# Sheet-2.net
KiCad netlist of a schematic drawn in Altium Designer
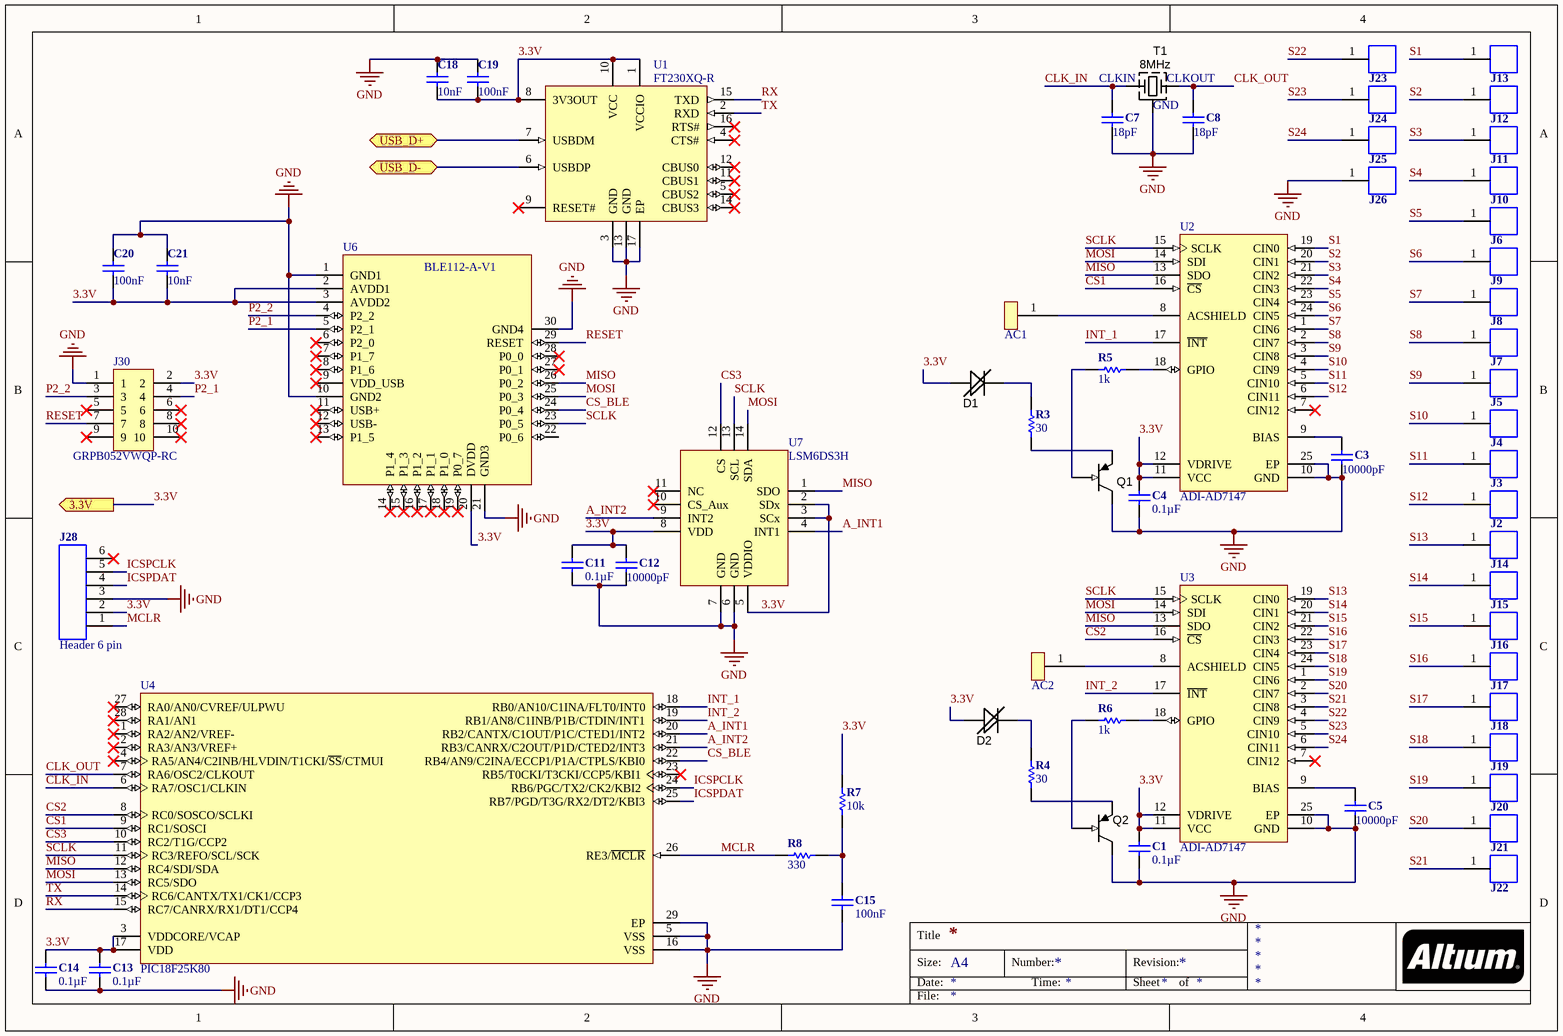
[diagram p0: Sheet-2.SchDoc]

(export (version "E")
  (design (tool "Eeschema 10.0.6"))
  (components
    (comp (ref "AC1")
      (value "AC_Shield")
      (footprint "AC_SHIELD")
      (libsource (lib "Glove") (part "AC_Shield"))
    )
    (comp (ref "AC2")
      (value "AC_Shield")
      (footprint "AC_SHIELD")
      (libsource (lib "Glove") (part "AC_Shield"))
    )
    (comp (ref "C1")
      (value "0.1µF")
      (footprint "CAP-0805(2012)-R")
      (description "___ OHM ___ mW 0805(2012) SMD")
      (fields
        (field (name "MANUFACTURER") "Yageo")
        (field (name "MANUFACTURER PART NUMBER") "CC0805KRX7R9BB104")
      )
      (libsource (lib "Glove") (part "C-0805(2012)"))
    )
    (comp (ref "C3")
      (value "10000pF")
      (footprint "CAP-0805(2012)-R")
      (description "___ OHM ___ mW 0805(2012) SMD")
      (fields
        (field (name "MANUFACTURER") "Yageo")
        (field (name "MANUFACTURER PART NUMBER") "CC0805KRX7R9BB103")
      )
      (libsource (lib "Glove") (part "C-0805(2012)"))
    )
    (comp (ref "C4")
      (value "0.1µF")
      (footprint "CAP-0805(2012)-R")
      (description "___ OHM ___ mW 0805(2012) SMD")
      (fields
        (field (name "MANUFACTURER") "Yageo")
        (field (name "MANUFACTURER PART NUMBER") "CC0805KRX7R9BB104")
      )
      (libsource (lib "Glove") (part "C-0805(2012)"))
    )
    (comp (ref "C5")
      (value "10000pF")
      (footprint "CAP-0805(2012)-R")
      (description "___ OHM ___ mW 0805(2012) SMD")
      (fields
        (field (name "MANUFACTURER") "Yageo")
        (field (name "MANUFACTURER PART NUMBER") "CC0805KRX7R9BB103")
      )
      (libsource (lib "Glove") (part "C-0805(2012)"))
    )
    (comp (ref "C7")
      (value "18pF")
      (footprint "CAP-0805(2012)-R")
      (description "___ OHM ___ mW 0805(2012) SMD")
      (fields
        (field (name "MANUFACTURER") "Yageo")
        (field (name "MANUFACTURER PART NUMBER") "CC0805JRNPO9BN180")
      )
      (libsource (lib "Glove") (part "C-0805(2012)"))
    )
    (comp (ref "C8")
      (value "18pF")
      (footprint "CAP-0805(2012)-R")
      (description "___ OHM ___ mW 0805(2012) SMD")
      (fields
        (field (name "MANUFACTURER") "Yageo")
        (field (name "MANUFACTURER PART NUMBER") "CC0805JRNPO9BN180")
      )
      (libsource (lib "Glove") (part "C-0805(2012)"))
    )
    (comp (ref "C11")
      (value "0.1µF")
      (footprint "CAP-0805(2012)-R")
      (description "___ OHM ___ mW 0805(2012) SMD")
      (fields
        (field (name "MANUFACTURER") "Yageo")
        (field (name "MANUFACTURER PART NUMBER") "CC0805KRX7R9BB104")
      )
      (libsource (lib "Glove") (part "C-0805(2012)"))
    )
    (comp (ref "C12")
      (value "10000pF")
      (footprint "CAP-0805(2012)-R")
      (description "___ OHM ___ mW 0805(2012) SMD")
      (fields
        (field (name "MANUFACTURER") "Yageo")
        (field (name "MANUFACTURER PART NUMBER") "CC0805KRX7R9BB103")
      )
      (libsource (lib "Glove") (part "C-0805(2012)"))
    )
    (comp (ref "C13")
      (value "0.1µF")
      (footprint "CAP-0805(2012)-R")
      (description "___ OHM ___ mW 0805(2012) SMD")
      (fields
        (field (name "MANUFACTURER") "Yageo")
        (field (name "MANUFACTURER PART NUMBER") "CC0805KRX7R9BB104")
      )
      (libsource (lib "Glove") (part "C-0805(2012)"))
    )
    (comp (ref "C14")
      (value "0.1µF")
      (footprint "CAP-0805(2012)-R")
      (description "___ OHM ___ mW 0805(2012) SMD")
      (fields
        (field (name "MANUFACTURER") "Yageo")
        (field (name "MANUFACTURER PART NUMBER") "CC0805KRX7R9BB104")
      )
      (libsource (lib "Glove") (part "C-0805(2012)"))
    )
    (comp (ref "C15")
      (value "100nF")
      (footprint "CAP-0805(2012)-R")
      (description "___ OHM ___ mW 0805(2012) SMD")
      (fields
        (field (name "MANUFACTURER") "Yageo")
        (field (name "MANUFACTURER PART NUMBER") "CC0805KRX7R9BB104")
      )
      (libsource (lib "Glove") (part "C-0805(2012)"))
    )
    (comp (ref "C18")
      (value "10nF")
      (footprint "CAP-0805(2012)-R")
      (description "___ OHM ___ mW 0805(2012) SMD")
      (fields
        (field (name "MANUFACTURER") "Yageo")
        (field (name "MANUFACTURER PART NUMBER") "CC0805KRX7R9BB103")
      )
      (libsource (lib "Glove") (part "C-0805(2012)"))
    )
    (comp (ref "C19")
      (value "100nF")
      (footprint "CAP-0805(2012)-R")
      (description "___ OHM ___ mW 0805(2012) SMD")
      (fields
        (field (name "MANUFACTURER") "Yageo")
        (field (name "MANUFACTURER PART NUMBER") "CC0805KRX7R9BB104")
      )
      (libsource (lib "Glove") (part "C-0805(2012)"))
    )
    (comp (ref "C20")
      (value "100nF")
      (footprint "CAP-0805(2012)-R")
      (description "___ OHM ___ mW 0805(2012) SMD")
      (fields
        (field (name "MANUFACTURER") "Yageo")
        (field (name "MANUFACTURER PART NUMBER") "CC0805KRX7R9BB104")
      )
      (libsource (lib "Glove") (part "C-0805(2012)"))
    )
    (comp (ref "C21")
      (value "10nF")
      (footprint "CAP-0805(2012)-R")
      (description "___ OHM ___ mW 0805(2012) SMD")
      (fields
        (field (name "MANUFACTURER") "Yageo")
        (field (name "MANUFACTURER PART NUMBER") "CC0805KRX7R9BB103")
      )
      (libsource (lib "Glove") (part "C-0805(2012)"))
    )
    (comp (ref "D1")
      (value "YELLOW")
      (footprint "LED-0805-A")
      (description "LED, 0805 SMD, YELLOW")
      (fields
        (field (name "MANUFACTURER") "OSRAM Opto Semiconductors Inc.")
        (field (name "MANUFACTURER PART NUMBER") "LY R976-PS-36")
      )
      (libsource (lib "Glove") (part "LED_0805_YELLOW"))
    )
    (comp (ref "D2")
      (value "YELLOW")
      (footprint "LED-0805-A")
      (description "LED, 0805 SMD, YELLOW")
      (fields
        (field (name "MANUFACTURER") "OSRAM Opto Semiconductors Inc.")
        (field (name "MANUFACTURER PART NUMBER") "LY R976-PS-36")
      )
      (libsource (lib "Glove") (part "LED_0805_YELLOW"))
    )
    (comp (ref "J2")
      (value "Conductive Thread")
      (footprint "THREAD_HOLE")
      (description "Header, 1 pin, Conductive Thread")
      (libsource (lib "Glove") (part "CON-1_Pin_Thread"))
    )
    (comp (ref "J3")
      (value "Conductive Thread")
      (footprint "THREAD_HOLE")
      (description "Header, 1 pin, Conductive Thread")
      (libsource (lib "Glove") (part "CON-1_Pin_Thread"))
    )
    (comp (ref "J4")
      (value "Conductive Thread")
      (footprint "THREAD_HOLE")
      (description "Header, 1 pin, Conductive Thread")
      (libsource (lib "Glove") (part "CON-1_Pin_Thread"))
    )
    (comp (ref "J5")
      (value "Conductive Thread")
      (footprint "THREAD_HOLE")
      (description "Header, 1 pin, Conductive Thread")
      (libsource (lib "Glove") (part "CON-1_Pin_Thread"))
    )
    (comp (ref "J6")
      (value "Conductive Thread")
      (footprint "THREAD_HOLE")
      (description "Header, 1 pin, Conductive Thread")
      (libsource (lib "Glove") (part "CON-1_Pin_Thread"))
    )
    (comp (ref "J7")
      (value "Conductive Thread")
      (footprint "THREAD_HOLE")
      (description "Header, 1 pin, Conductive Thread")
      (libsource (lib "Glove") (part "CON-1_Pin_Thread"))
    )
    (comp (ref "J8")
      (value "Conductive Thread")
      (footprint "THREAD_HOLE")
      (description "Header, 1 pin, Conductive Thread")
      (libsource (lib "Glove") (part "CON-1_Pin_Thread"))
    )
    (comp (ref "J9")
      (value "Conductive Thread")
      (footprint "THREAD_HOLE")
      (description "Header, 1 pin, Conductive Thread")
      (libsource (lib "Glove") (part "CON-1_Pin_Thread"))
    )
    (comp (ref "J10")
      (value "Conductive Thread")
      (footprint "THREAD_HOLE")
      (description "Header, 1 pin, Conductive Thread")
      (libsource (lib "Glove") (part "CON-1_Pin_Thread"))
    )
    (comp (ref "J11")
      (value "Conductive Thread")
      (footprint "THREAD_HOLE")
      (description "Header, 1 pin, Conductive Thread")
      (libsource (lib "Glove") (part "CON-1_Pin_Thread"))
    )
    (comp (ref "J12")
      (value "Conductive Thread")
      (footprint "THREAD_HOLE")
      (description "Header, 1 pin, Conductive Thread")
      (libsource (lib "Glove") (part "CON-1_Pin_Thread"))
    )
    (comp (ref "J13")
      (value "Conductive Thread")
      (footprint "THREAD_HOLE")
      (description "Header, 1 pin, Conductive Thread")
      (libsource (lib "Glove") (part "CON-1_Pin_Thread"))
    )
    (comp (ref "J14")
      (value "Conductive Thread")
      (footprint "THREAD_HOLE")
      (description "Header, 1 pin, Conductive Thread")
      (libsource (lib "Glove") (part "CON-1_Pin_Thread"))
    )
    (comp (ref "J15")
      (value "Conductive Thread")
      (footprint "THREAD_HOLE")
      (description "Header, 1 pin, Conductive Thread")
      (libsource (lib "Glove") (part "CON-1_Pin_Thread"))
    )
    (comp (ref "J16")
      (value "Conductive Thread")
      (footprint "THREAD_HOLE")
      (description "Header, 1 pin, Conductive Thread")
      (libsource (lib "Glove") (part "CON-1_Pin_Thread"))
    )
    (comp (ref "J17")
      (value "Conductive Thread")
      (footprint "THREAD_HOLE")
      (description "Header, 1 pin, Conductive Thread")
      (libsource (lib "Glove") (part "CON-1_Pin_Thread"))
    )
    (comp (ref "J18")
      (value "Conductive Thread")
      (footprint "THREAD_HOLE")
      (description "Header, 1 pin, Conductive Thread")
      (libsource (lib "Glove") (part "CON-1_Pin_Thread"))
    )
    (comp (ref "J19")
      (value "Conductive Thread")
      (footprint "THREAD_HOLE")
      (description "Header, 1 pin, Conductive Thread")
      (libsource (lib "Glove") (part "CON-1_Pin_Thread"))
    )
    (comp (ref "J20")
      (value "Conductive Thread")
      (footprint "THREAD_HOLE")
      (description "Header, 1 pin, Conductive Thread")
      (libsource (lib "Glove") (part "CON-1_Pin_Thread"))
    )
    (comp (ref "J21")
      (value "Conductive Thread")
      (footprint "THREAD_HOLE")
      (description "Header, 1 pin, Conductive Thread")
      (libsource (lib "Glove") (part "CON-1_Pin_Thread"))
    )
    (comp (ref "J22")
      (value "Conductive Thread")
      (footprint "THREAD_HOLE")
      (description "Header, 1 pin, Conductive Thread")
      (libsource (lib "Glove") (part "CON-1_Pin_Thread"))
    )
    (comp (ref "J23")
      (value "Conductive Thread")
      (footprint "THREAD_HOLE")
      (description "Header, 1 pin, Conductive Thread")
      (libsource (lib "Glove") (part "CON-1_Pin_Thread"))
    )
    (comp (ref "J24")
      (value "Conductive Thread")
      (footprint "THREAD_HOLE")
      (description "Header, 1 pin, Conductive Thread")
      (libsource (lib "Glove") (part "CON-1_Pin_Thread"))
    )
    (comp (ref "J25")
      (value "Conductive Thread")
      (footprint "THREAD_HOLE")
      (description "Header, 1 pin, Conductive Thread")
      (libsource (lib "Glove") (part "CON-1_Pin_Thread"))
    )
    (comp (ref "J26")
      (value "Conductive Thread")
      (footprint "THREAD_HOLE")
      (description "Header, 1 pin, Conductive Thread")
      (libsource (lib "Glove") (part "CON-1_Pin_Thread"))
    )
    (comp (ref "J28")
      (value "Header 6 pin")
      (footprint "HEADER-6-100mil")
      (description "Header, 6 pin, .1 pitch")
      (fields
        (field (name "MANUFACTURER") "Amphenol FCI")
        (field (name "MANUFACTURER PART NUMBER") "68000-406HLF")
      )
      (libsource (lib "Glove") (part "CON-6Pin-100Mil"))
    )
    (comp (ref "J30")
      (value "GRPB052VWQP-RC")
      (footprint "GRPB052VWQP-RC")
      (description "CONN HEADER .050\" 10PS DL SMD AU")
      (fields (field (name "MANUFACTURER") "Sullins Connector Solutions"))
      (libsource (lib "UCSD Protolab") (part "GRPB052VWQP-RC"))
    )
    (comp (ref "Q1")
      (value "~")
      (footprint "SOT23-3")
      (description "Transistor PNP")
      (fields
        (field (name "MANUFACTURER") "Diodes Incorporated")
        (field (name "MANUFACTURER PART NUMBER") "FMMT591TA")
      )
      (libsource (lib "Glove") (part "FMMT591CT-ND"))
    )
    (comp (ref "Q2")
      (value "~")
      (footprint "SOT23-3")
      (description "Transistor PNP")
      (fields
        (field (name "MANUFACTURER") "Diodes Incorporated")
        (field (name "MANUFACTURER PART NUMBER") "FMMT591TA")
      )
      (libsource (lib "Glove") (part "FMMT591CT-ND"))
    )
    (comp (ref "R3")
      (value "30")
      (footprint "R-0805(2012)-R")
      (description "___ OHM ___ mW 0805(2012) SMD")
      (fields
        (field (name "MANUFACTURER") "Yageo")
        (field (name "MANUFACTURER PART NUMBER") "RC0805JR-0730RL")
      )
      (libsource (lib "Glove") (part "R-0805(2012)"))
    )
    (comp (ref "R4")
      (value "30")
      (footprint "R-0805(2012)-R")
      (description "___ OHM ___ mW 0805(2012) SMD")
      (fields
        (field (name "MANUFACTURER") "Yageo")
        (field (name "MANUFACTURER PART NUMBER") "RC0805JR-0730RL")
      )
      (libsource (lib "Glove") (part "R-0805(2012)"))
    )
    (comp (ref "R5")
      (value "1k")
      (footprint "R-0805(2012)-R")
      (description "___ OHM ___ mW 0805(2012) SMD")
      (fields
        (field (name "MANUFACTURER") "Yageo")
        (field (name "MANUFACTURER PART NUMBER") "RC0805JR-071KL")
      )
      (libsource (lib "Glove") (part "R-0805(2012)"))
    )
    (comp (ref "R6")
      (value "1k")
      (footprint "R-0805(2012)-R")
      (description "___ OHM ___ mW 0805(2012) SMD")
      (fields
        (field (name "MANUFACTURER") "Yageo")
        (field (name "MANUFACTURER PART NUMBER") "RC0805JR-071KL")
      )
      (libsource (lib "Glove") (part "R-0805(2012)"))
    )
    (comp (ref "R7")
      (value "10k")
      (footprint "R-0805(2012)-R")
      (description "___ OHM ___ mW 0805(2012) SMD")
      (fields
        (field (name "MANUFACTURER") "Yageo")
        (field (name "MANUFACTURER PART NUMBER") "RC0805FR-0710KL")
      )
      (libsource (lib "Glove") (part "R-0805(2012)"))
    )
    (comp (ref "R8")
      (value "330")
      (footprint "R-0805(2012)-R")
      (description "___ OHM ___ mW 0805(2012) SMD")
      (fields
        (field (name "MANUFACTURER") "Yageo")
        (field (name "MANUFACTURER PART NUMBER") "RC0805JR-07330RL")
      )
      (libsource (lib "Glove") (part "R-0805(2012)"))
    )
    (comp (ref "T1")
      (value "8MHz")
      (footprint "CRYSTAL-8MHZ")
      (description "Oscillator Crystal 8MHz 10ppm")
      (fields
        (field (name "MANUFACTURER") "Abracon LLC")
        (field (name "MANUFACTURER PART NUMBER") "ABMM2-8.000MHZ-E2-T")
      )
      (libsource (lib "Glove") (part "CRYSTAL_8MHz"))
    )
    (comp (ref "U1")
      (value "FT230XQ-R")
      (footprint "QFN-16")
      (fields (field (name "MANUFACTURER") "FTDI, Future Technology Devices International Ltd"))
      (libsource (lib "Glove") (part "FT230XQ-R"))
    )
    (comp (ref "U2")
      (value "ADI-AD7147")
      (footprint "LFCSP_WQ")
      (fields
        (field (name "MANUFACTURER") "Analog Devices Inc.")
        (field (name "MANUFACTURER PART NUMBER") "AD7147PACPZ-500R7")
      )
      (libsource (lib "Glove") (part "ADI-AD7147"))
    )
    (comp (ref "U3")
      (value "ADI-AD7147")
      (footprint "LFCSP_WQ")
      (fields
        (field (name "MANUFACTURER") "Analog Devices Inc.")
        (field (name "MANUFACTURER PART NUMBER") "AD7147PACPZ-500R7")
      )
      (libsource (lib "Glove") (part "ADI-AD7147"))
    )
    (comp (ref "U4")
      (value "PIC18F25K80")
      (footprint "MCHP-QFN-S-MM28_N")
      (fields
        (field (name "MANUFACTURER") "Microchip Technology")
        (field (name "MANUFACTURER PART NUMBER") "PIC18F25K80T-I/MM")
      )
      (libsource (lib "Glove") (part "PIC18F25K80"))
    )
    (comp (ref "U6")
      (value "BLE112-A-V1")
      (footprint "BLE112-A-V1")
      (description "CLASS 2 BLTOOTH 4.0 MODULE")
      (fields (field (name "MANUFACTURER") "Silicon Labs"))
      (libsource (lib "UCSD Protolab") (part "BLE112-A-V1"))
    )
    (comp (ref "U7")
      (value "LSM6DS3H")
      (footprint "LGA-14")
      (description "3D accelerometer and 3D gyroscope")
      (fields
        (field (name "MANUFACTURER") "STMicroelectronics")
        (field (name "MANUFACTURER PART NUMBER") "LSM6DS3HTR")
      )
      (libsource (lib "Glove") (part "LSM6DS3H"))
    )
  )
  (nets
    (net (code "1") (name "/3.3V") (class "Default")
      (node (ref "C1") (pin "1") (pinfunction "1_1") (pintype "passive"))
      (node (ref "C11") (pin "2") (pinfunction "2_2") (pintype "passive"))
      (node (ref "C12") (pin "2") (pinfunction "2_2") (pintype "passive"))
      (node (ref "C13") (pin "1") (pinfunction "1_1") (pintype "passive"))
      (node (ref "C14") (pin "1") (pinfunction "1_1") (pintype "passive"))
      (node (ref "C18") (pin "2") (pinfunction "2_2") (pintype "passive"))
      (node (ref "C19") (pin "2") (pinfunction "2_2") (pintype "passive"))
      (node (ref "C20") (pin "2") (pinfunction "2_2") (pintype "passive"))
      (node (ref "C21") (pin "2") (pinfunction "2_2") (pintype "passive"))
      (node (ref "C4") (pin "1") (pinfunction "1_1") (pintype "passive"))
      (node (ref "D1") (pin "A") (pinfunction "A_A") (pintype "passive"))
      (node (ref "D2") (pin "A") (pinfunction "A_A") (pintype "passive"))
      (node (ref "J28") (pin "2") (pinfunction "2_2") (pintype "passive"))
      (node (ref "J30") (pin "2") (pinfunction "2_2") (pintype "passive"))
      (node (ref "R7") (pin "2") (pinfunction "2_2") (pintype "passive"))
      (node (ref "U1") (pin "1") (pinfunction "VCCIO_1") (pintype "power_in"))
      (node (ref "U1") (pin "10") (pinfunction "VCC_10") (pintype "power_in"))
      (node (ref "U1") (pin "8") (pinfunction "3V3OUT_8") (pintype "power_in"))
      (node (ref "U2") (pin "11") (pinfunction "VCC_11") (pintype "power_in"))
      (node (ref "U2") (pin "12") (pinfunction "VDRIVE_12") (pintype "power_in"))
      (node (ref "U3") (pin "11") (pinfunction "VCC_11") (pintype "power_in"))
      (node (ref "U3") (pin "12") (pinfunction "VDRIVE_12") (pintype "power_in"))
      (node (ref "U4") (pin "17") (pinfunction "VDD_17") (pintype "power_in"))
      (node (ref "U4") (pin "3") (pinfunction "VDDCORE/VCAP_3") (pintype "power_in"))
      (node (ref "U6") (pin "2") (pinfunction "AVDD1_2") (pintype "power_in"))
      (node (ref "U6") (pin "20") (pinfunction "DVDD_20") (pintype "power_in"))
      (node (ref "U6") (pin "3") (pinfunction "AVDD2_3") (pintype "power_in"))
      (node (ref "U7") (pin "2") (pinfunction "SDx_2") (pintype "passive"))
      (node (ref "U7") (pin "3") (pinfunction "SCx_3") (pintype "passive"))
      (node (ref "U7") (pin "5") (pinfunction "VDDIO_5") (pintype "passive"))
      (node (ref "U7") (pin "8") (pinfunction "VDD_8") (pintype "passive"))
    )
    (net (code "2") (name "/A_INT1") (class "Default")
      (node (ref "U4") (pin "20") (pinfunction "RB2/CANTX/C1OUT/P1C/CTED1/INT2_20") (pintype "bidirectional"))
      (node (ref "U7") (pin "4") (pinfunction "INT1_4") (pintype "passive"))
    )
    (net (code "3") (name "/A_INT2") (class "Default")
      (node (ref "U4") (pin "21") (pinfunction "RB3/CANRX/C2OUT/P1D/CTED2/INT3_21") (pintype "bidirectional"))
      (node (ref "U7") (pin "9") (pinfunction "INT2_9") (pintype "passive"))
    )
    (net (code "4") (name "/CLK_IN") (class "Default")
      (node (ref "C7") (pin "1") (pinfunction "1_1") (pintype "passive"))
      (node (ref "T1") (pin "1") (pinfunction "CLKIN_1") (pintype "passive"))
      (node (ref "U4") (pin "6") (pinfunction "RA7/OSC1/CLKIN_6") (pintype "bidirectional"))
    )
    (net (code "5") (name "/CLK_OUT") (class "Default")
      (node (ref "C8") (pin "1") (pinfunction "1_1") (pintype "passive"))
      (node (ref "T1") (pin "3") (pinfunction "X_3") (pintype "passive"))
      (node (ref "U4") (pin "7") (pinfunction "RA6/OSC2/CLKOUT_7") (pintype "bidirectional"))
    )
    (net (code "6") (name "/CS1") (class "Default")
      (node (ref "U2") (pin "16") (pinfunction "~{CS}_16") (pintype "input"))
      (node (ref "U4") (pin "9") (pinfunction "RC1/SOSCI_9") (pintype "bidirectional"))
    )
    (net (code "7") (name "/CS2") (class "Default")
      (node (ref "U3") (pin "16") (pinfunction "~{CS}_16") (pintype "input"))
      (node (ref "U4") (pin "8") (pinfunction "RC0/SOSCO/SCLKI_8") (pintype "bidirectional"))
    )
    (net (code "8") (name "/CS3") (class "Default")
      (node (ref "U4") (pin "10") (pinfunction "RC2/T1G/CCP2_10") (pintype "bidirectional"))
      (node (ref "U7") (pin "12") (pinfunction "CS_12") (pintype "passive"))
    )
    (net (code "9") (name "/CS_BLE") (class "Default")
      (node (ref "U4") (pin "22") (pinfunction "RB4/AN9/C2INA/ECCP1/P1A/CTPLS/KBI0_22") (pintype "bidirectional"))
      (node (ref "U6") (pin "24") (pinfunction "P0_4_24") (pintype "bidirectional"))
    )
    (net (code "10") (name "/ICSPCLK") (class "Default")
      (node (ref "J28") (pin "5") (pinfunction "5_5") (pintype "passive"))
      (node (ref "U4") (pin "24") (pinfunction "RB6/PGC/TX2/CK2/KBI2_24") (pintype "bidirectional"))
    )
    (net (code "11") (name "/ICSPDAT") (class "Default")
      (node (ref "J28") (pin "4") (pinfunction "4_4") (pintype "passive"))
      (node (ref "U4") (pin "25") (pinfunction "RB7/PGD/T3G/RX2/DT2/KBI3_25") (pintype "bidirectional"))
    )
    (net (code "12") (name "/INT_1") (class "Default")
      (node (ref "U2") (pin "17") (pinfunction "~{INT}_17") (pintype "open_collector"))
      (node (ref "U4") (pin "18") (pinfunction "RB0/AN10/C1INA/FLT0/INT0_18") (pintype "bidirectional"))
    )
    (net (code "13") (name "/INT_2") (class "Default")
      (node (ref "U3") (pin "17") (pinfunction "~{INT}_17") (pintype "open_collector"))
      (node (ref "U4") (pin "19") (pinfunction "RB1/AN8/C1INB/P1B/CTDIN/INT1_19") (pintype "bidirectional"))
    )
    (net (code "14") (name "/MCLR") (class "Default")
      (node (ref "J28") (pin "1") (pinfunction "1_1") (pintype "passive"))
      (node (ref "R8") (pin "1") (pinfunction "1_1") (pintype "passive"))
      (node (ref "U4") (pin "26") (pinfunction "RE3/~{MCLR}_26") (pintype "input"))
    )
    (net (code "15") (name "/MISO") (class "Default")
      (node (ref "U2") (pin "13") (pinfunction "SDO_13") (pintype "tri_state"))
      (node (ref "U3") (pin "13") (pinfunction "SDO_13") (pintype "tri_state"))
      (node (ref "U4") (pin "12") (pinfunction "RC4/SDI/SDA_12") (pintype "bidirectional"))
      (node (ref "U6") (pin "26") (pinfunction "P0_2_26") (pintype "bidirectional"))
      (node (ref "U7") (pin "1") (pinfunction "SDO_1") (pintype "passive"))
    )
    (net (code "16") (name "/MOSI") (class "Default")
      (node (ref "U2") (pin "14") (pinfunction "SDI_14") (pintype "input"))
      (node (ref "U3") (pin "14") (pinfunction "SDI_14") (pintype "input"))
      (node (ref "U4") (pin "13") (pinfunction "RC5/SDO_13") (pintype "bidirectional"))
      (node (ref "U6") (pin "25") (pinfunction "P0_3_25") (pintype "bidirectional"))
      (node (ref "U7") (pin "14") (pinfunction "SDA_14") (pintype "passive"))
    )
    (net (code "17") (name "/P2_1") (class "Default")
      (node (ref "J30") (pin "4") (pinfunction "4_4") (pintype "passive"))
      (node (ref "U6") (pin "5") (pinfunction "P2_1_5") (pintype "bidirectional"))
    )
    (net (code "18") (name "/P2_2") (class "Default")
      (node (ref "J30") (pin "3") (pinfunction "3_3") (pintype "passive"))
      (node (ref "U6") (pin "4") (pinfunction "P2_2_4") (pintype "bidirectional"))
    )
    (net (code "19") (name "/RESET") (class "Default")
      (node (ref "J30") (pin "7") (pinfunction "7_7") (pintype "passive"))
      (node (ref "U6") (pin "29") (pinfunction "RESET_29") (pintype "bidirectional"))
    )
    (net (code "20") (name "/RX") (class "Default")
      (node (ref "U1") (pin "15") (pinfunction "TXD_15") (pintype "output"))
      (node (ref "U4") (pin "15") (pinfunction "RC7/CANRX/RX1/DT1/CCP4_15") (pintype "bidirectional"))
    )
    (net (code "21") (name "/S1") (class "Default")
      (node (ref "J13") (pin "1") (pinfunction "1_1") (pintype "passive"))
      (node (ref "U2") (pin "19") (pinfunction "CIN0_19") (pintype "input"))
    )
    (net (code "22") (name "/S2") (class "Default")
      (node (ref "J12") (pin "1") (pinfunction "1_1") (pintype "passive"))
      (node (ref "U2") (pin "20") (pinfunction "CIN1_20") (pintype "input"))
    )
    (net (code "23") (name "/S3") (class "Default")
      (node (ref "J11") (pin "1") (pinfunction "1_1") (pintype "passive"))
      (node (ref "U2") (pin "21") (pinfunction "CIN2_21") (pintype "input"))
    )
    (net (code "24") (name "/S4") (class "Default")
      (node (ref "J10") (pin "1") (pinfunction "1_1") (pintype "passive"))
      (node (ref "U2") (pin "22") (pinfunction "CIN3_22") (pintype "input"))
    )
    (net (code "25") (name "/S5") (class "Default")
      (node (ref "J6") (pin "1") (pinfunction "1_1") (pintype "passive"))
      (node (ref "U2") (pin "23") (pinfunction "CIN4_23") (pintype "input"))
    )
    (net (code "26") (name "/S6") (class "Default")
      (node (ref "J9") (pin "1") (pinfunction "1_1") (pintype "passive"))
      (node (ref "U2") (pin "24") (pinfunction "CIN5_24") (pintype "input"))
    )
    (net (code "27") (name "/S7") (class "Default")
      (node (ref "J8") (pin "1") (pinfunction "1_1") (pintype "passive"))
      (node (ref "U2") (pin "1") (pinfunction "CIN6_1") (pintype "input"))
    )
    (net (code "28") (name "/S8") (class "Default")
      (node (ref "J7") (pin "1") (pinfunction "1_1") (pintype "passive"))
      (node (ref "U2") (pin "2") (pinfunction "CIN7_2") (pintype "input"))
    )
    (net (code "29") (name "/S9") (class "Default")
      (node (ref "J5") (pin "1") (pinfunction "1_1") (pintype "passive"))
      (node (ref "U2") (pin "3") (pinfunction "CIN8_3") (pintype "input"))
    )
    (net (code "30") (name "/S10") (class "Default")
      (node (ref "J4") (pin "1") (pinfunction "1_1") (pintype "passive"))
      (node (ref "U2") (pin "4") (pinfunction "CIN9_4") (pintype "input"))
    )
    (net (code "31") (name "/S11") (class "Default")
      (node (ref "J3") (pin "1") (pinfunction "1_1") (pintype "passive"))
      (node (ref "U2") (pin "5") (pinfunction "CIN10_5") (pintype "input"))
    )
    (net (code "32") (name "/S12") (class "Default")
      (node (ref "J2") (pin "1") (pinfunction "1_1") (pintype "passive"))
      (node (ref "U2") (pin "6") (pinfunction "CIN11_6") (pintype "input"))
    )
    (net (code "33") (name "/S13") (class "Default")
      (node (ref "J14") (pin "1") (pinfunction "1_1") (pintype "passive"))
      (node (ref "U3") (pin "19") (pinfunction "CIN0_19") (pintype "input"))
    )
    (net (code "34") (name "/S14") (class "Default")
      (node (ref "J15") (pin "1") (pinfunction "1_1") (pintype "passive"))
      (node (ref "U3") (pin "20") (pinfunction "CIN1_20") (pintype "input"))
    )
    (net (code "35") (name "/S15") (class "Default")
      (node (ref "J16") (pin "1") (pinfunction "1_1") (pintype "passive"))
      (node (ref "U3") (pin "21") (pinfunction "CIN2_21") (pintype "input"))
    )
    (net (code "36") (name "/S16") (class "Default")
      (node (ref "J17") (pin "1") (pinfunction "1_1") (pintype "passive"))
      (node (ref "U3") (pin "22") (pinfunction "CIN3_22") (pintype "input"))
    )
    (net (code "37") (name "/S17") (class "Default")
      (node (ref "J18") (pin "1") (pinfunction "1_1") (pintype "passive"))
      (node (ref "U3") (pin "23") (pinfunction "CIN4_23") (pintype "input"))
    )
    (net (code "38") (name "/S18") (class "Default")
      (node (ref "J19") (pin "1") (pinfunction "1_1") (pintype "passive"))
      (node (ref "U3") (pin "24") (pinfunction "CIN5_24") (pintype "input"))
    )
    (net (code "39") (name "/S19") (class "Default")
      (node (ref "J20") (pin "1") (pinfunction "1_1") (pintype "passive"))
      (node (ref "U3") (pin "1") (pinfunction "CIN6_1") (pintype "input"))
    )
    (net (code "40") (name "/S20") (class "Default")
      (node (ref "J21") (pin "1") (pinfunction "1_1") (pintype "passive"))
      (node (ref "U3") (pin "2") (pinfunction "CIN7_2") (pintype "input"))
    )
    (net (code "41") (name "/S21") (class "Default")
      (node (ref "J22") (pin "1") (pinfunction "1_1") (pintype "passive"))
      (node (ref "U3") (pin "3") (pinfunction "CIN8_3") (pintype "input"))
    )
    (net (code "42") (name "/S22") (class "Default")
      (node (ref "J23") (pin "1") (pinfunction "1_1") (pintype "passive"))
      (node (ref "U3") (pin "4") (pinfunction "CIN9_4") (pintype "input"))
    )
    (net (code "43") (name "/S23") (class "Default")
      (node (ref "J24") (pin "1") (pinfunction "1_1") (pintype "passive"))
      (node (ref "U3") (pin "5") (pinfunction "CIN10_5") (pintype "input"))
    )
    (net (code "44") (name "/S24") (class "Default")
      (node (ref "J25") (pin "1") (pinfunction "1_1") (pintype "passive"))
      (node (ref "U3") (pin "6") (pinfunction "CIN11_6") (pintype "input"))
    )
    (net (code "45") (name "/SCLK") (class "Default")
      (node (ref "U2") (pin "15") (pinfunction "SCLK_15") (pintype "input"))
      (node (ref "U3") (pin "15") (pinfunction "SCLK_15") (pintype "input"))
      (node (ref "U4") (pin "11") (pinfunction "RC3/REFO/SCL/SCK_11") (pintype "bidirectional"))
      (node (ref "U6") (pin "23") (pinfunction "P0_5_23") (pintype "bidirectional"))
      (node (ref "U7") (pin "13") (pinfunction "SCL_13") (pintype "passive"))
    )
    (net (code "46") (name "/TX") (class "Default")
      (node (ref "U1") (pin "2") (pinfunction "RXD_2") (pintype "input"))
      (node (ref "U4") (pin "14") (pinfunction "RC6/CANTX/TX1/CK1/CCP3_14") (pintype "bidirectional"))
    )
    (net (code "47") (name "/USB_D+") (class "Default")
      (node (ref "U1") (pin "7") (pinfunction "USBDM_7") (pintype "input"))
    )
    (net (code "48") (name "/USB_D-") (class "Default")
      (node (ref "U1") (pin "6") (pinfunction "USBDP_6") (pintype "input"))
    )
    (net (code "49") (name "GND") (class "Default")
      (node (ref "C1") (pin "2") (pinfunction "2_2") (pintype "passive"))
      (node (ref "C11") (pin "1") (pinfunction "1_1") (pintype "passive"))
      (node (ref "C12") (pin "1") (pinfunction "1_1") (pintype "passive"))
      (node (ref "C13") (pin "2") (pinfunction "2_2") (pintype "passive"))
      (node (ref "C14") (pin "2") (pinfunction "2_2") (pintype "passive"))
      (node (ref "C15") (pin "2") (pinfunction "2_2") (pintype "passive"))
      (node (ref "C18") (pin "1") (pinfunction "1_1") (pintype "passive"))
      (node (ref "C19") (pin "1") (pinfunction "1_1") (pintype "passive"))
      (node (ref "C20") (pin "1") (pinfunction "1_1") (pintype "passive"))
      (node (ref "C21") (pin "1") (pinfunction "1_1") (pintype "passive"))
      (node (ref "C3") (pin "2") (pinfunction "2_2") (pintype "passive"))
      (node (ref "C4") (pin "2") (pinfunction "2_2") (pintype "passive"))
      (node (ref "C5") (pin "2") (pinfunction "2_2") (pintype "passive"))
      (node (ref "C7") (pin "2") (pinfunction "2_2") (pintype "passive"))
      (node (ref "C8") (pin "2") (pinfunction "2_2") (pintype "passive"))
      (node (ref "J26") (pin "1") (pinfunction "1_1") (pintype "passive"))
      (node (ref "J28") (pin "3") (pinfunction "3_3") (pintype "passive"))
      (node (ref "J30") (pin "1") (pinfunction "1_1") (pintype "passive"))
      (node (ref "Q1") (pin "2") (pinfunction "C_2") (pintype "passive"))
      (node (ref "Q2") (pin "2") (pinfunction "C_2") (pintype "passive"))
      (node (ref "T1") (pin "2") (pinfunction "GND_2") (pintype "passive"))
      (node (ref "U1") (pin "13") (pinfunction "GND_13") (pintype "power_in"))
      (node (ref "U1") (pin "17") (pinfunction "EP_17") (pintype "power_in"))
      (node (ref "U1") (pin "3") (pinfunction "GND_3") (pintype "power_in"))
      (node (ref "U2") (pin "10") (pinfunction "GND_10") (pintype "power_in"))
      (node (ref "U2") (pin "25") (pinfunction "EP_25") (pintype "power_in"))
      (node (ref "U3") (pin "10") (pinfunction "GND_10") (pintype "power_in"))
      (node (ref "U3") (pin "25") (pinfunction "EP_25") (pintype "power_in"))
      (node (ref "U4") (pin "16") (pinfunction "VSS_16") (pintype "power_in"))
      (node (ref "U4") (pin "29") (pinfunction "EP_29") (pintype "power_in"))
      (node (ref "U4") (pin "5") (pinfunction "VSS_5") (pintype "power_in"))
      (node (ref "U6") (pin "1") (pinfunction "GND1_1") (pintype "power_in"))
      (node (ref "U6") (pin "10") (pinfunction "GND2_10") (pintype "power_in"))
      (node (ref "U6") (pin "21") (pinfunction "GND3_21") (pintype "power_in"))
      (node (ref "U6") (pin "30") (pinfunction "GND4_30") (pintype "power_in"))
      (node (ref "U7") (pin "6") (pinfunction "GND_6") (pintype "passive"))
      (node (ref "U7") (pin "7") (pinfunction "GND_7") (pintype "passive"))
    )
    (net (code "50") (name "Net-(AC1-9)") (class "Default")
      (node (ref "AC1") (pin "1") (pinfunction "9_1") (pintype "passive"))
      (node (ref "U2") (pin "8") (pinfunction "ACSHIELD_8") (pintype "passive"))
    )
    (net (code "51") (name "Net-(AC2-9)") (class "Default")
      (node (ref "AC2") (pin "1") (pinfunction "9_1") (pintype "passive"))
      (node (ref "U3") (pin "8") (pinfunction "ACSHIELD_8") (pintype "passive"))
    )
    (net (code "52") (name "Net-(C15-Pad1)") (class "Default")
      (node (ref "C15") (pin "1") (pinfunction "1_1") (pintype "passive"))
      (node (ref "R7") (pin "1") (pinfunction "1_1") (pintype "passive"))
      (node (ref "R8") (pin "2") (pinfunction "2_2") (pintype "passive"))
    )
    (net (code "53") (name "Net-(D1-PadK)") (class "Default")
      (node (ref "D1") (pin "K") (pinfunction "K_K") (pintype "passive"))
      (node (ref "R3") (pin "2") (pinfunction "2_2") (pintype "passive"))
    )
    (net (code "54") (name "Net-(D2-PadK)") (class "Default")
      (node (ref "D2") (pin "K") (pinfunction "K_K") (pintype "passive"))
      (node (ref "R4") (pin "2") (pinfunction "2_2") (pintype "passive"))
    )
    (net (code "55") (name "Net-(Q1-B)") (class "Default")
      (node (ref "Q1") (pin "1") (pinfunction "B_1") (pintype "input"))
      (node (ref "R5") (pin "1") (pinfunction "1_1") (pintype "passive"))
    )
    (net (code "56") (name "Net-(Q1-E)") (class "Default")
      (node (ref "Q1") (pin "3") (pinfunction "E_3") (pintype "passive"))
      (node (ref "R3") (pin "1") (pinfunction "1_1") (pintype "passive"))
    )
    (net (code "57") (name "Net-(Q2-B)") (class "Default")
      (node (ref "Q2") (pin "1") (pinfunction "B_1") (pintype "input"))
      (node (ref "R6") (pin "2") (pinfunction "2_2") (pintype "passive"))
    )
    (net (code "58") (name "Net-(Q2-E)") (class "Default")
      (node (ref "Q2") (pin "3") (pinfunction "E_3") (pintype "passive"))
      (node (ref "R4") (pin "1") (pinfunction "1_1") (pintype "passive"))
    )
    (net (code "59") (name "Net-(U2-BIAS)") (class "Default")
      (node (ref "C3") (pin "1") (pinfunction "1_1") (pintype "passive"))
      (node (ref "U2") (pin "9") (pinfunction "BIAS_9") (pintype "passive"))
    )
    (net (code "60") (name "Net-(U2-GPIO)") (class "Default")
      (node (ref "R5") (pin "2") (pinfunction "2_2") (pintype "passive"))
      (node (ref "U2") (pin "18") (pinfunction "GPIO_18") (pintype "bidirectional"))
    )
    (net (code "61") (name "Net-(U3-BIAS)") (class "Default")
      (node (ref "C5") (pin "1") (pinfunction "1_1") (pintype "passive"))
      (node (ref "U3") (pin "9") (pinfunction "BIAS_9") (pintype "passive"))
    )
    (net (code "62") (name "Net-(U3-GPIO)") (class "Default")
      (node (ref "R6") (pin "1") (pinfunction "1_1") (pintype "passive"))
      (node (ref "U3") (pin "18") (pinfunction "GPIO_18") (pintype "bidirectional"))
    )
    (net (code "63") (name "unconnected-(J28-Pad6)") (class "Default")
      (node (ref "J28") (pin "6") (pinfunction "6_6") (pintype "passive+no_connect"))
    )
    (net (code "64") (name "unconnected-(J30-Pad5)") (class "Default")
      (node (ref "J30") (pin "5") (pinfunction "5_5") (pintype "passive+no_connect"))
    )
    (net (code "65") (name "unconnected-(J30-Pad6)") (class "Default")
      (node (ref "J30") (pin "6") (pinfunction "6_6") (pintype "passive+no_connect"))
    )
    (net (code "66") (name "unconnected-(J30-Pad8)") (class "Default")
      (node (ref "J30") (pin "8") (pinfunction "8_8") (pintype "passive+no_connect"))
    )
    (net (code "67") (name "unconnected-(J30-Pad9)") (class "Default")
      (node (ref "J30") (pin "9") (pinfunction "9_9") (pintype "passive+no_connect"))
    )
    (net (code "68") (name "unconnected-(J30-Pad10)") (class "Default")
      (node (ref "J30") (pin "10") (pinfunction "10_10") (pintype "passive+no_connect"))
    )
    (net (code "69") (name "unconnected-(U1-CBUS0-Pad12)") (class "Default")
      (node (ref "U1") (pin "12") (pinfunction "CBUS0_12") (pintype "bidirectional+no_connect"))
    )
    (net (code "70") (name "unconnected-(U1-CBUS1-Pad11)") (class "Default")
      (node (ref "U1") (pin "11") (pinfunction "CBUS1_11") (pintype "bidirectional+no_connect"))
    )
    (net (code "71") (name "unconnected-(U1-CBUS2-Pad5)") (class "Default")
      (node (ref "U1") (pin "5") (pinfunction "CBUS2_5") (pintype "bidirectional+no_connect"))
    )
    (net (code "72") (name "unconnected-(U1-CBUS3-Pad14)") (class "Default")
      (node (ref "U1") (pin "14") (pinfunction "CBUS3_14") (pintype "bidirectional+no_connect"))
    )
    (net (code "73") (name "unconnected-(U1-CTS#-Pad4)") (class "Default")
      (node (ref "U1") (pin "4") (pinfunction "CTS#_4") (pintype "input+no_connect"))
    )
    (net (code "74") (name "unconnected-(U1-RESET#-Pad9)") (class "Default")
      (node (ref "U1") (pin "9") (pinfunction "RESET#_9") (pintype "passive+no_connect"))
    )
    (net (code "75") (name "unconnected-(U1-RTS#-Pad16)") (class "Default")
      (node (ref "U1") (pin "16") (pinfunction "RTS#_16") (pintype "output+no_connect"))
    )
    (net (code "76") (name "unconnected-(U2-CIN12-Pad7)") (class "Default")
      (node (ref "U2") (pin "7") (pinfunction "CIN12_7") (pintype "input+no_connect"))
    )
    (net (code "77") (name "unconnected-(U3-CIN12-Pad7)") (class "Default")
      (node (ref "U3") (pin "7") (pinfunction "CIN12_7") (pintype "input+no_connect"))
    )
    (net (code "78") (name "unconnected-(U4-RA0{slash}AN0{slash}CVREF{slash}ULPWU-Pad27)") (class "Default")
      (node (ref "U4") (pin "27") (pinfunction "RA0/AN0/CVREF/ULPWU_27") (pintype "bidirectional+no_connect"))
    )
    (net (code "79") (name "unconnected-(U4-RA1{slash}AN1-Pad28)") (class "Default")
      (node (ref "U4") (pin "28") (pinfunction "RA1/AN1_28") (pintype "bidirectional+no_connect"))
    )
    (net (code "80") (name "unconnected-(U4-RA2{slash}AN2{slash}VREF--Pad1)") (class "Default")
      (node (ref "U4") (pin "1") (pinfunction "RA2/AN2/VREF-_1") (pintype "bidirectional+no_connect"))
    )
    (net (code "81") (name "unconnected-(U4-RA3{slash}AN3{slash}VREF+-Pad2)") (class "Default")
      (node (ref "U4") (pin "2") (pinfunction "RA3/AN3/VREF+_2") (pintype "bidirectional+no_connect"))
    )
    (net (code "82") (name "unconnected-(U4-RA5{slash}AN4{slash}C2INB{slash}HLVDIN{slash}T1CKI{slash}~{SS}{slash}CTMUI-Pad4)") (class "Default")
      (node (ref "U4") (pin "4") (pinfunction "RA5/AN4/C2INB/HLVDIN/T1CKI/~{SS}/CTMUI_4") (pintype "bidirectional+no_connect"))
    )
    (net (code "83") (name "unconnected-(U4-RB5{slash}T0CKI{slash}T3CKI{slash}CCP5{slash}KBI1-Pad23)") (class "Default")
      (node (ref "U4") (pin "23") (pinfunction "RB5/T0CKI/T3CKI/CCP5/KBI1_23") (pintype "bidirectional+no_connect"))
    )
    (net (code "84") (name "unconnected-(U6-P0_0-Pad28)") (class "Default")
      (node (ref "U6") (pin "28") (pinfunction "P0_0_28") (pintype "bidirectional+no_connect"))
    )
    (net (code "85") (name "unconnected-(U6-P0_1-Pad27)") (class "Default")
      (node (ref "U6") (pin "27") (pinfunction "P0_1_27") (pintype "bidirectional+no_connect"))
    )
    (net (code "86") (name "unconnected-(U6-P0_6-Pad22)") (class "Default")
      (node (ref "U6") (pin "22") (pinfunction "P0_6_22") (pintype "bidirectional"))
    )
    (net (code "87") (name "unconnected-(U6-P0_7-Pad19)") (class "Default")
      (node (ref "U6") (pin "19") (pinfunction "P0_7_19") (pintype "bidirectional+no_connect"))
    )
    (net (code "88") (name "unconnected-(U6-P1_0-Pad18)") (class "Default")
      (node (ref "U6") (pin "18") (pinfunction "P1_0_18") (pintype "bidirectional+no_connect"))
    )
    (net (code "89") (name "unconnected-(U6-P1_1-Pad17)") (class "Default")
      (node (ref "U6") (pin "17") (pinfunction "P1_1_17") (pintype "bidirectional+no_connect"))
    )
    (net (code "90") (name "unconnected-(U6-P1_2-Pad16)") (class "Default")
      (node (ref "U6") (pin "16") (pinfunction "P1_2_16") (pintype "bidirectional+no_connect"))
    )
    (net (code "91") (name "unconnected-(U6-P1_3-Pad15)") (class "Default")
      (node (ref "U6") (pin "15") (pinfunction "P1_3_15") (pintype "bidirectional+no_connect"))
    )
    (net (code "92") (name "unconnected-(U6-P1_4-Pad14)") (class "Default")
      (node (ref "U6") (pin "14") (pinfunction "P1_4_14") (pintype "bidirectional+no_connect"))
    )
    (net (code "93") (name "unconnected-(U6-P1_5-Pad13)") (class "Default")
      (node (ref "U6") (pin "13") (pinfunction "P1_5_13") (pintype "bidirectional+no_connect"))
    )
    (net (code "94") (name "unconnected-(U6-P1_6-Pad8)") (class "Default")
      (node (ref "U6") (pin "8") (pinfunction "P1_6_8") (pintype "bidirectional+no_connect"))
    )
    (net (code "95") (name "unconnected-(U6-P1_7-Pad7)") (class "Default")
      (node (ref "U6") (pin "7") (pinfunction "P1_7_7") (pintype "bidirectional+no_connect"))
    )
    (net (code "96") (name "unconnected-(U6-P2_0-Pad6)") (class "Default")
      (node (ref "U6") (pin "6") (pinfunction "P2_0_6") (pintype "bidirectional+no_connect"))
    )
    (net (code "97") (name "unconnected-(U6-USB+-Pad11)") (class "Default")
      (node (ref "U6") (pin "11") (pinfunction "USB+_11") (pintype "bidirectional+no_connect"))
    )
    (net (code "98") (name "unconnected-(U6-USB--Pad12)") (class "Default")
      (node (ref "U6") (pin "12") (pinfunction "USB-_12") (pintype "bidirectional+no_connect"))
    )
    (net (code "99") (name "unconnected-(U6-VDD_USB-Pad9)") (class "Default")
      (node (ref "U6") (pin "9") (pinfunction "VDD_USB_9") (pintype "power_in+no_connect"))
    )
    (net (code "100") (name "unconnected-(U7-CS_Aux-Pad10)") (class "Default")
      (node (ref "U7") (pin "10") (pinfunction "CS_Aux_10") (pintype "passive+no_connect"))
    )
    (net (code "101") (name "unconnected-(U7-NC-Pad11)") (class "Default")
      (node (ref "U7") (pin "11") (pinfunction "NC_11") (pintype "passive+no_connect"))
    )
  )
)
